# ETHERNET_W5500.net
KiCad netlist of a schematic drawn in Altium Designer
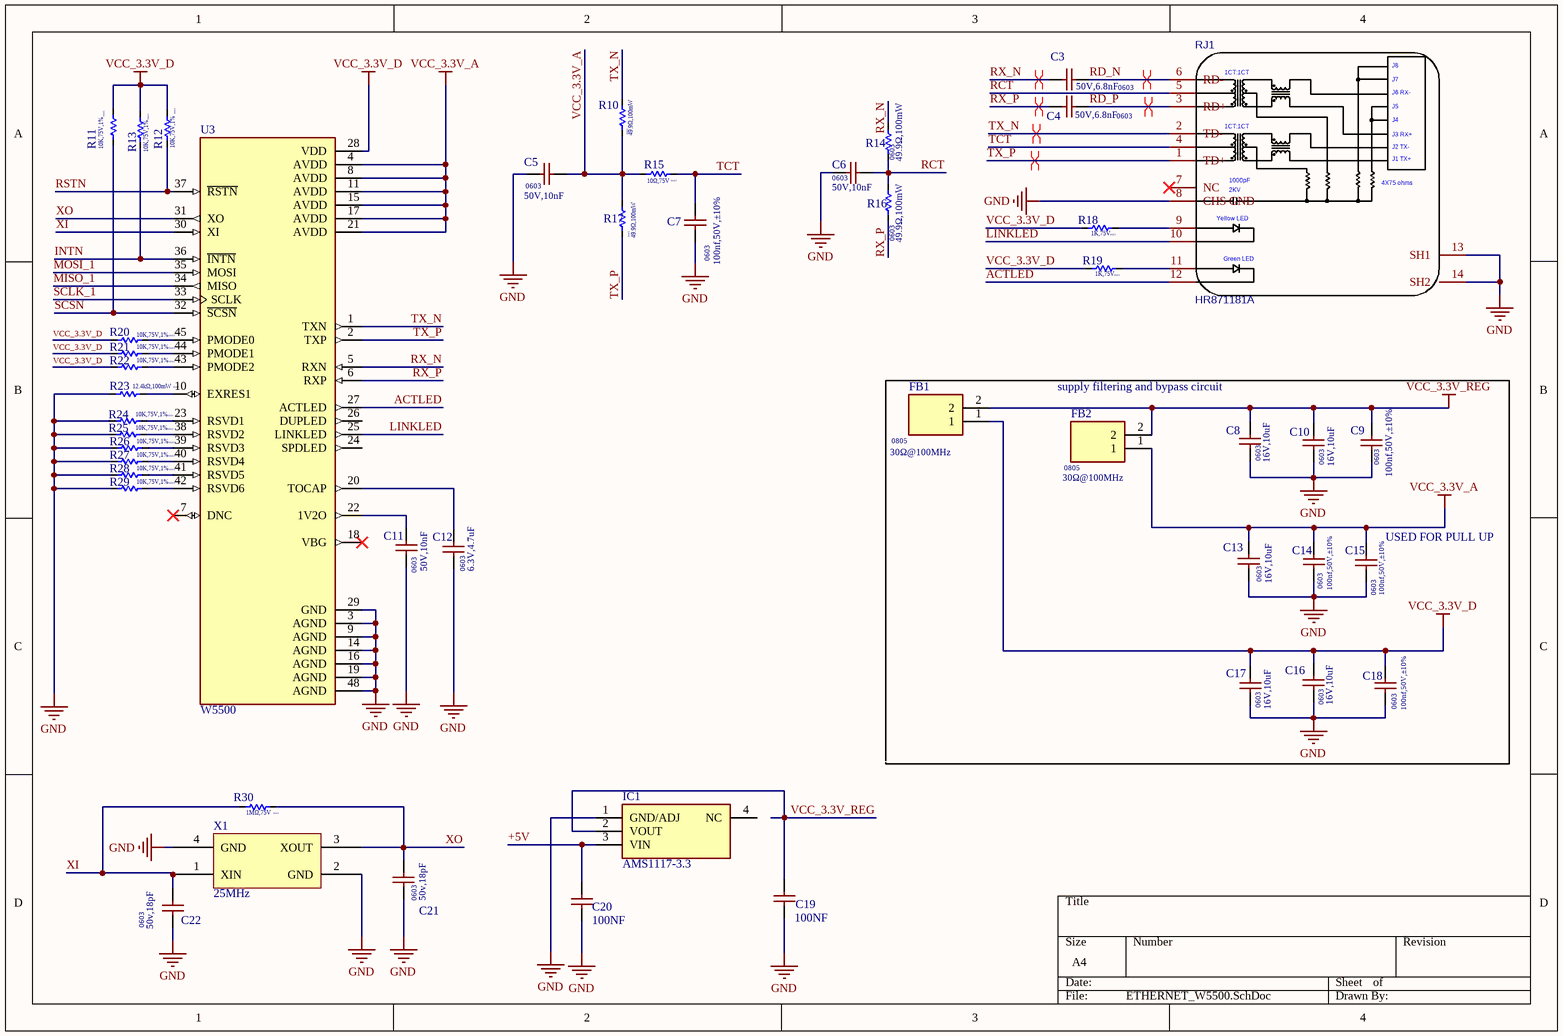
[diagram p0: ETHERNET_W5500.SchDoc]

(export (version "E")
  (design (tool "Eeschema 10.0.6"))
  (components
    (comp (ref "C3")
      (value "50V,6.8nF")
      (footprint "CAPC1608X90N")
      (description "50V 6.8nF X7R ±10% 0603 Multilayer Ceramic Capacitors MLCC - SMD/SMT ROHS")
      (fields
        (field (name "MANUFACTURER") "Walsin Tech Corp")
        (field (name "MPN") "0603B682K500CT")
        (field (name "PACKAGE") "0603")
      )
      (libsource (lib "RCL") (part "0603B682K500CT"))
    )
    (comp (ref "C4")
      (value "50V,6.8nF")
      (footprint "CAPC1608X90N")
      (description "50V 6.8nF X7R ±10% 0603 Multilayer Ceramic Capacitors MLCC - SMD/SMT ROHS")
      (fields
        (field (name "MANUFACTURER") "Walsin Tech Corp")
        (field (name "MPN") "0603B682K500CT")
        (field (name "PACKAGE") "0603")
      )
      (libsource (lib "RCL") (part "0603B682K500CT"))
    )
    (comp (ref "C5")
      (value "50V,10nF")
      (footprint "CAPC1608X90N")
      (description "50V 10nF X7R ±20% 0603 Multilayer Ceramic Capacitors MLCC - SMD/SMT ROHS")
      (fields
        (field (name "MANUFACTURER") "CCTC")
        (field (name "MPN") "TCC0603X7R103M500CT")
        (field (name "PACKAGE") "0603")
      )
      (libsource (lib "RCL") (part "TCC0603X7R103M500CT"))
    )
    (comp (ref "C6")
      (value "50V,10nF")
      (footprint "CAPC1608X90N")
      (description "50V 10nF X7R ±20% 0603 Multilayer Ceramic Capacitors MLCC - SMD/SMT ROHS")
      (fields
        (field (name "MANUFACTURER") "CCTC")
        (field (name "MPN") "TCC0603X7R103M500CT")
        (field (name "PACKAGE") "0603")
      )
      (libsource (lib "RCL") (part "TCC0603X7R103M500CT"))
    )
    (comp (ref "C7")
      (value "100nf,50V,±10%")
      (footprint "C0603")
      (description "50V 100nF X7R ±10% 0603 Multilayer Ceramic Capacitors MLCC - SMD/SMT ROHS")
      (fields
        (field (name "MPN") "603-CC603KRX7R9BB104")
        (field (name "MANUFACTURER") "KEMET")
        (field (name "PACKAGE") "0603")
      )
      (libsource (lib "RCL") (part "CC0603KRX7R9BB104"))
    )
    (comp (ref "C8")
      (value "16V,10uF")
      (footprint "CAPC1608X90N")
      (description "16V 10uF Y5V ±20% 0603 Multilayer Ceramic Capacitors MLCC - SMD/SMT ROHS")
      (fields
        (field (name "MANUFACTURER") "KEMET")
        (field (name "MPN") "CC0603KRX7R9BB104")
        (field (name "PACKAGE") "0603")
      )
      (libsource (lib "RCL") (part "0603F106M160NT"))
    )
    (comp (ref "C9")
      (value "100nf,50V,±10%")
      (footprint "C0603")
      (description "50V 100nF X7R ±10% 0603 Multilayer Ceramic Capacitors MLCC - SMD/SMT ROHS")
      (fields
        (field (name "MPN") "603-CC603KRX7R9BB104")
        (field (name "MANUFACTURER") "KEMET")
        (field (name "PACKAGE") "0603")
      )
      (libsource (lib "RCL") (part "CC0603KRX7R9BB104"))
    )
    (comp (ref "C10")
      (value "16V,10uF")
      (footprint "CAPC1608X90N")
      (description "16V 10uF Y5V ±20% 0603 Multilayer Ceramic Capacitors MLCC - SMD/SMT ROHS")
      (fields
        (field (name "MANUFACTURER") "KEMET")
        (field (name "MPN") "CC0603KRX7R9BB104")
        (field (name "PACKAGE") "0603")
      )
      (libsource (lib "RCL") (part "0603F106M160NT"))
    )
    (comp (ref "C11")
      (value "50V,10nF")
      (footprint "CAPC1608X90N")
      (description "50V 10nF X7R ±20% 0603 Multilayer Ceramic Capacitors MLCC - SMD/SMT ROHS")
      (fields
        (field (name "MANUFACTURER") "CCTC")
        (field (name "MPN") "TCC0603X7R103M500CT")
        (field (name "PACKAGE") "0603")
      )
      (libsource (lib "RCL") (part "TCC0603X7R103M500CT"))
    )
    (comp (ref "C12")
      (value "6.3V,4.7uF")
      (footprint "CAPC1608X90N")
      (description "Capacitor")
      (fields
        (field (name "MANUFACTURER") "Samsung Electro-Mechanics")
        (field (name "MPN") "CL10A475KQ8NNNC")
        (field (name "PACKAGE") "0603")
      )
      (libsource (lib "RCL") (part "CL10A475KQ8NNNC"))
    )
    (comp (ref "C13")
      (value "16V,10uF")
      (footprint "CAPC1608X90N")
      (description "16V 10uF Y5V ±20% 0603 Multilayer Ceramic Capacitors MLCC - SMD/SMT ROHS")
      (fields
        (field (name "MANUFACTURER") "KEMET")
        (field (name "MPN") "CC0603KRX7R9BB104")
        (field (name "PACKAGE") "0603")
      )
      (libsource (lib "RCL") (part "0603F106M160NT"))
    )
    (comp (ref "C14")
      (value "100nf,50V,±10%")
      (footprint "C0603")
      (description "50V 100nF X7R ±10% 0603 Multilayer Ceramic Capacitors MLCC - SMD/SMT ROHS")
      (fields
        (field (name "MPN") "603-CC603KRX7R9BB104")
        (field (name "MANUFACTURER") "KEMET")
        (field (name "PACKAGE") "0603")
      )
      (libsource (lib "RCL") (part "CC0603KRX7R9BB104"))
    )
    (comp (ref "C15")
      (value "100nf,50V,±10%")
      (footprint "C0603")
      (description "50V 100nF X7R ±10% 0603 Multilayer Ceramic Capacitors MLCC - SMD/SMT ROHS")
      (fields
        (field (name "MPN") "603-CC603KRX7R9BB104")
        (field (name "MANUFACTURER") "KEMET")
        (field (name "PACKAGE") "0603")
      )
      (libsource (lib "RCL") (part "CC0603KRX7R9BB104"))
    )
    (comp (ref "C16")
      (value "16V,10uF")
      (footprint "CAPC1608X90N")
      (description "16V 10uF Y5V ±20% 0603 Multilayer Ceramic Capacitors MLCC - SMD/SMT ROHS")
      (fields
        (field (name "MANUFACTURER") "KEMET")
        (field (name "MPN") "CC0603KRX7R9BB104")
        (field (name "PACKAGE") "0603")
      )
      (libsource (lib "RCL") (part "0603F106M160NT"))
    )
    (comp (ref "C17")
      (value "16V,10uF")
      (footprint "CAPC1608X90N")
      (description "16V 10uF Y5V ±20% 0603 Multilayer Ceramic Capacitors MLCC - SMD/SMT ROHS")
      (fields
        (field (name "MANUFACTURER") "KEMET")
        (field (name "MPN") "CC0603KRX7R9BB104")
        (field (name "PACKAGE") "0603")
      )
      (libsource (lib "RCL") (part "0603F106M160NT"))
    )
    (comp (ref "C18")
      (value "100nf,50V,±10%")
      (footprint "C0603")
      (description "50V 100nF X7R ±10% 0603 Multilayer Ceramic Capacitors MLCC - SMD/SMT ROHS")
      (fields
        (field (name "MPN") "603-CC603KRX7R9BB104")
        (field (name "MANUFACTURER") "KEMET")
        (field (name "PACKAGE") "0603")
      )
      (libsource (lib "RCL") (part "CC0603KRX7R9BB104"))
    )
    (comp (ref "C19")
      (value "100NF")
      (footprint "C0603")
      (description "50V 100nF X7R ±10% 0603 Multilayer Ceramic Capacitors MLCC - SMD/SMT ROHS")
      (fields (field (name "MPN") "603-CC603KRX7R9BB104") (field (name "MANUFACTURER") "KEMET"))
      (libsource (lib "RCL") (part "CC0603KRX7R9BB104"))
    )
    (comp (ref "C20")
      (value "100NF")
      (footprint "C0603")
      (description "50V 100nF X7R ±10% 0603 Multilayer Ceramic Capacitors MLCC - SMD/SMT ROHS")
      (fields (field (name "MPN") "603-CC603KRX7R9BB104") (field (name "MANUFACTURER") "KEMET"))
      (libsource (lib "RCL") (part "CC0603KRX7R9BB104"))
    )
    (comp (ref "C21")
      (value "50v,18pF")
      (footprint "CAPC1608X90N")
      (description "50V 18pF NP0 ±5% 0603 Multilayer Ceramic Capacitors MLCC - SMD/SMT ROHS")
      (fields
        (field (name "MANUFACTURER") "YAGEO")
        (field (name "MPN") "CC0603JRNPO9BN180")
        (field (name "PACKAGE") "0603")
      )
      (libsource (lib "RCL") (part "CC0603JRNPO9BN180"))
    )
    (comp (ref "C22")
      (value "50v,18pF")
      (footprint "CAPC1608X90N")
      (description "50V 18pF NP0 ±5% 0603 Multilayer Ceramic Capacitors MLCC - SMD/SMT ROHS")
      (fields
        (field (name "MANUFACTURER") "YAGEO")
        (field (name "MPN") "CC0603JRNPO9BN180")
        (field (name "PACKAGE") "0603")
      )
      (libsource (lib "RCL") (part "CC0603JRNPO9BN180"))
    )
    (comp (ref "FB1")
      (value "30Ω@100MHz")
      (footprint "BEADC2012X105N")
      (description "Ferrite Bead")
      (fields
        (field (name "MANUFACTURER") "Murata Electronics")
        (field (name "MPN") "BLM21PG300SN1D")
        (field (name "PACKAGE") "0805")
      )
      (libsource (lib "RCL") (part "BLM21PG300SN1D"))
    )
    (comp (ref "FB2")
      (value "30Ω@100MHz")
      (footprint "BEADC2012X105N")
      (description "Ferrite Bead")
      (fields
        (field (name "MANUFACTURER") "Murata Electronics")
        (field (name "MPN") "BLM21PG300SN1D")
        (field (name "PACKAGE") "0805")
      )
      (libsource (lib "RCL") (part "BLM21PG300SN1D"))
    )
    (comp (ref "IC1")
      (value "AMS1117-3.3")
      (footprint "IC:SOT229P700X180-4N")
      (description "Integrated Circuit")
      (fields (field (name "MANUFACTURER") "Advanced"))
      (libsource (lib "IC") (part "AMS1117-3.3"))
    )
    (comp (ref "R10")
      (value "49.9Ω,100mW")
      (footprint "R0603")
      (description "100mW Thick Film Resistors ±100ppm/℃ ±1% 49.9Ω 0603 Chip Resistor - Surface Mount ROHS")
      (fields
        (field (name "MANUFACTURER") "Panasonic")
        (field (name "MPN") "ERJ-3EKF49R9V")
        (field (name "PACKAGE") "0603")
      )
      (libsource (lib "RCL") (part "ERJ-3EKF49R9V"))
    )
    (comp (ref "R11")
      (value "10K,75V,1%")
      (footprint "R0603")
      (description "100mW Thick Film Resistors ±100ppm/℃ ±1% 10kΩ 0603 Chip Resistor - Surface Mount ROHS")
      (fields
        (field (name "MPN") "0603WAF1002T5E")
        (field (name "MANUFACTURER") "UNI-ROYAL(Uniroyal Elec)")
        (field (name "PACKAGE") "0603")
      )
      (libsource (lib "RCL") (part "0603WAF1002T5E"))
    )
    (comp (ref "R12")
      (value "10K,75V,1%")
      (footprint "R0603")
      (description "100mW Thick Film Resistors ±100ppm/℃ ±1% 10kΩ 0603 Chip Resistor - Surface Mount ROHS")
      (fields
        (field (name "MPN") "0603WAF1002T5E")
        (field (name "MANUFACTURER") "UNI-ROYAL(Uniroyal Elec)")
        (field (name "PACKAGE") "0603")
      )
      (libsource (lib "RCL") (part "0603WAF1002T5E"))
    )
    (comp (ref "R13")
      (value "10K,75V,1%")
      (footprint "R0603")
      (description "100mW Thick Film Resistors ±100ppm/℃ ±1% 10kΩ 0603 Chip Resistor - Surface Mount ROHS")
      (fields
        (field (name "MPN") "0603WAF1002T5E")
        (field (name "MANUFACTURER") "UNI-ROYAL(Uniroyal Elec)")
        (field (name "PACKAGE") "0603")
      )
      (libsource (lib "RCL") (part "0603WAF1002T5E"))
    )
    (comp (ref "R14")
      (value "49.9Ω,100mW")
      (footprint "R0603")
      (description "100mW Thick Film Resistors ±100ppm/℃ ±1% 49.9Ω 0603 Chip Resistor - Surface Mount ROHS")
      (fields
        (field (name "MANUFACTURER") "Panasonic")
        (field (name "MPN") "ERJ-3EKF49R9V")
        (field (name "PACKAGE") "0603")
      )
      (libsource (lib "RCL") (part "ERJ-3EKF49R9V"))
    )
    (comp (ref "R15")
      (value "10Ω,75V")
      (footprint "R0603")
      (fields
        (field (name "MANUFACTURER") "Ever Ohms Tech")
        (field (name "MPN") "QR0603J10R0P05Z")
        (field (name "PACKAGE") "0603")
        (field (name "Comment") "10R")
      )
      (libsource (lib "RCL") (part "QR0603J10R0P05Z"))
    )
    (comp (ref "R16")
      (value "49.9Ω,100mW")
      (footprint "R0603")
      (description "100mW Thick Film Resistors ±100ppm/℃ ±1% 49.9Ω 0603 Chip Resistor - Surface Mount ROHS")
      (fields
        (field (name "MANUFACTURER") "Panasonic")
        (field (name "MPN") "ERJ-3EKF49R9V")
        (field (name "PACKAGE") "0603")
      )
      (libsource (lib "RCL") (part "ERJ-3EKF49R9V"))
    )
    (comp (ref "R17")
      (value "49.9Ω,100mW")
      (footprint "R0603")
      (description "100mW Thick Film Resistors ±100ppm/℃ ±1% 49.9Ω 0603 Chip Resistor - Surface Mount ROHS")
      (fields
        (field (name "MANUFACTURER") "Panasonic")
        (field (name "MPN") "ERJ-3EKF49R9V")
        (field (name "PACKAGE") "0603")
      )
      (libsource (lib "RCL") (part "ERJ-3EKF49R9V"))
    )
    (comp (ref "R18")
      (value "1K,75V")
      (footprint "R0603")
      (description "100mW Thick Film Resistors 75V ±100ppm/℃ ±1% 1kΩ 0603 Chip Resistor - Surface Mount ROHS")
      (fields
        (field (name "MANUFACTURER") "UNI-ROYAL(Uniroyal Elec)")
        (field (name "MPN") "0603WAF1001T5E")
        (field (name "PACKAGE") "0603")
      )
      (libsource (lib "RCL") (part "0603WAF1001T5E"))
    )
    (comp (ref "R19")
      (value "1K,75V")
      (footprint "R0603")
      (description "100mW Thick Film Resistors 75V ±100ppm/℃ ±1% 1kΩ 0603 Chip Resistor - Surface Mount ROHS")
      (fields
        (field (name "MANUFACTURER") "UNI-ROYAL(Uniroyal Elec)")
        (field (name "MPN") "0603WAF1001T5E")
        (field (name "PACKAGE") "0603")
      )
      (libsource (lib "RCL") (part "0603WAF1001T5E"))
    )
    (comp (ref "R20")
      (value "10K,75V,1%")
      (footprint "R0603")
      (description "100mW Thick Film Resistors ±100ppm/℃ ±1% 10kΩ 0603 Chip Resistor - Surface Mount ROHS")
      (fields
        (field (name "MPN") "0603WAF1002T5E")
        (field (name "MANUFACTURER") "UNI-ROYAL(Uniroyal Elec)")
        (field (name "PACKAGE") "0603")
      )
      (libsource (lib "RCL") (part "0603WAF1002T5E"))
    )
    (comp (ref "R21")
      (value "10K,75V,1%")
      (footprint "R0603")
      (description "100mW Thick Film Resistors ±100ppm/℃ ±1% 10kΩ 0603 Chip Resistor - Surface Mount ROHS")
      (fields
        (field (name "MPN") "0603WAF1002T5E")
        (field (name "MANUFACTURER") "UNI-ROYAL(Uniroyal Elec)")
        (field (name "PACKAGE") "0603")
      )
      (libsource (lib "RCL") (part "0603WAF1002T5E"))
    )
    (comp (ref "R22")
      (value "10K,75V,1%")
      (footprint "R0603")
      (description "100mW Thick Film Resistors ±100ppm/℃ ±1% 10kΩ 0603 Chip Resistor - Surface Mount ROHS")
      (fields
        (field (name "MPN") "0603WAF1002T5E")
        (field (name "MANUFACTURER") "UNI-ROYAL(Uniroyal Elec)")
        (field (name "PACKAGE") "0603")
      )
      (libsource (lib "RCL") (part "0603WAF1002T5E"))
    )
    (comp (ref "R23")
      (value "12.4kΩ,100mW")
      (footprint "R0603")
      (description "Resistor")
      (fields
        (field (name "MANUFACTURER") "Panasonic")
        (field (name "MPN") "ERJ-3EKF1242V")
        (field (name "PACKAGE") "0603")
      )
      (libsource (lib "RCL") (part "ERJ-3EKF1242V"))
    )
    (comp (ref "R24")
      (value "10K,75V,1%")
      (footprint "R0603")
      (description "100mW Thick Film Resistors ±100ppm/℃ ±1% 10kΩ 0603 Chip Resistor - Surface Mount ROHS")
      (fields
        (field (name "MPN") "0603WAF1002T5E")
        (field (name "MANUFACTURER") "UNI-ROYAL(Uniroyal Elec)")
        (field (name "PACKAGE") "0603")
      )
      (libsource (lib "RCL") (part "0603WAF1002T5E"))
    )
    (comp (ref "R25")
      (value "10K,75V,1%")
      (footprint "R0603")
      (description "100mW Thick Film Resistors ±100ppm/℃ ±1% 10kΩ 0603 Chip Resistor - Surface Mount ROHS")
      (fields
        (field (name "MPN") "0603WAF1002T5E")
        (field (name "MANUFACTURER") "UNI-ROYAL(Uniroyal Elec)")
        (field (name "PACKAGE") "0603")
      )
      (libsource (lib "RCL") (part "0603WAF1002T5E"))
    )
    (comp (ref "R26")
      (value "10K,75V,1%")
      (footprint "R0603")
      (description "100mW Thick Film Resistors ±100ppm/℃ ±1% 10kΩ 0603 Chip Resistor - Surface Mount ROHS")
      (fields
        (field (name "MPN") "0603WAF1002T5E")
        (field (name "MANUFACTURER") "UNI-ROYAL(Uniroyal Elec)")
        (field (name "PACKAGE") "0603")
      )
      (libsource (lib "RCL") (part "0603WAF1002T5E"))
    )
    (comp (ref "R27")
      (value "10K,75V,1%")
      (footprint "R0603")
      (description "100mW Thick Film Resistors ±100ppm/℃ ±1% 10kΩ 0603 Chip Resistor - Surface Mount ROHS")
      (fields
        (field (name "MPN") "0603WAF1002T5E")
        (field (name "MANUFACTURER") "UNI-ROYAL(Uniroyal Elec)")
        (field (name "PACKAGE") "0603")
      )
      (libsource (lib "RCL") (part "0603WAF1002T5E"))
    )
    (comp (ref "R28")
      (value "10K,75V,1%")
      (footprint "R0603")
      (description "100mW Thick Film Resistors ±100ppm/℃ ±1% 10kΩ 0603 Chip Resistor - Surface Mount ROHS")
      (fields
        (field (name "MPN") "0603WAF1002T5E")
        (field (name "MANUFACTURER") "UNI-ROYAL(Uniroyal Elec)")
        (field (name "PACKAGE") "0603")
      )
      (libsource (lib "RCL") (part "0603WAF1002T5E"))
    )
    (comp (ref "R29")
      (value "10K,75V,1%")
      (footprint "R0603")
      (description "100mW Thick Film Resistors ±100ppm/℃ ±1% 10kΩ 0603 Chip Resistor - Surface Mount ROHS")
      (fields
        (field (name "MPN") "0603WAF1002T5E")
        (field (name "MANUFACTURER") "UNI-ROYAL(Uniroyal Elec)")
        (field (name "PACKAGE") "0603")
      )
      (libsource (lib "RCL") (part "0603WAF1002T5E"))
    )
    (comp (ref "R30")
      (value "1MΩ,75V")
      (footprint "R0603")
      (description "100mW Thick Film Resistors ±100ppm/℃ ±1% 1MΩ 0603 Chip Resistor - Surface Mount ROHS")
      (fields
        (field (name "MANUFACTURER") "UNI-ROYAL(Uniroyal Elec)")
        (field (name "MPN") "0603WAF1002T5E")
        (field (name "PACKAGE") "0603")
      )
      (libsource (lib "RCL") (part "0603WAF1004T5E"))
    )
    (comp (ref "RJ1")
      (value "HR871181A")
      (footprint "HR871181A_mirror")
      (fields (field (name "BOM_SUPPLIER PART") "C49312"))
      (libsource (lib "connector_button") (part "HR871181A_mirror"))
    )
    (comp (ref "U3")
      (value "W5500")
      (footprint "W5500 Ethernet")
      (description "Ethernet Controller 10/100 Base-T/TX PHY SPI Interface 48-LQFP (7x7)")
      (fields (field (name "MF") "WIZnet"))
      (libsource (lib "IC_MODULE") (part "W5500"))
    )
    (comp (ref "X1")
      (value "25MHz")
      (footprint "SMD Crystal")
      (description "25MHz SMD Crystal Resonator 18pF 60Ω ±10ppm ±30ppm -40℃~+85℃ SMD3225-4P Crystals ROHS")
      (libsource (lib "RCL") (part "3TJ425000XYFBC"))
    )
  )
  (nets
    (net (code "1") (name "/+5V") (class "Default")
      (node (ref "C20") (pin "1") (pinfunction "1_1") (pintype "passive"))
      (node (ref "IC1") (pin "3") (pinfunction "VIN_3") (pintype "passive"))
    )
    (net (code "2") (name "/ACTLED") (class "Default")
      (node (ref "RJ1") (pin "12") (pinfunction "12_12") (pintype "passive"))
      (node (ref "U3") (pin "27") (pinfunction "ACTLED_27") (pintype "output"))
    )
    (net (code "3") (name "/INTN") (class "Default")
      (node (ref "R13") (pin "1") (pinfunction "1_1") (pintype "passive"))
      (node (ref "U3") (pin "36") (pinfunction "~{INTN}_36") (pintype "input"))
    )
    (net (code "4") (name "/LINKLED") (class "Default")
      (node (ref "RJ1") (pin "10") (pinfunction "10_10") (pintype "passive"))
      (node (ref "U3") (pin "25") (pinfunction "LINKLED_25") (pintype "output"))
    )
    (net (code "5") (name "/MISO_1") (class "Default")
      (node (ref "U3") (pin "34") (pinfunction "MISO_34") (pintype "output"))
    )
    (net (code "6") (name "/MOSI_1") (class "Default")
      (node (ref "U3") (pin "35") (pinfunction "MOSI_35") (pintype "input"))
    )
    (net (code "7") (name "/RCT") (class "Default")
      (node (ref "C6") (pin "2") (pinfunction "2_2") (pintype "passive"))
      (node (ref "R14") (pin "1") (pinfunction "1_1") (pintype "passive"))
      (node (ref "R16") (pin "2") (pinfunction "2_2") (pintype "passive"))
      (node (ref "RJ1") (pin "5") (pinfunction "5_5") (pintype "passive"))
    )
    (net (code "8") (name "/RD_N") (class "Default")
      (node (ref "C3") (pin "2") (pinfunction "2_2") (pintype "passive"))
      (node (ref "RJ1") (pin "6") (pinfunction "RD-_6") (pintype "passive"))
    )
    (net (code "9") (name "/RD_P") (class "Default")
      (node (ref "C4") (pin "2") (pinfunction "2_2") (pintype "passive"))
      (node (ref "RJ1") (pin "3") (pinfunction "RD+_3") (pintype "passive"))
    )
    (net (code "10") (name "/RSTN") (class "Default")
      (node (ref "R12") (pin "1") (pinfunction "1_1") (pintype "passive"))
      (node (ref "U3") (pin "37") (pinfunction "~{RSTN}_37") (pintype "input"))
    )
    (net (code "11") (name "/RX_N") (class "Default")
      (node (ref "C3") (pin "1") (pinfunction "1_1") (pintype "passive"))
      (node (ref "R14") (pin "2") (pinfunction "2_2") (pintype "passive"))
      (node (ref "U3") (pin "5") (pinfunction "RXN_5") (pintype "input"))
    )
    (net (code "12") (name "/RX_P") (class "Default")
      (node (ref "C4") (pin "1") (pinfunction "1_1") (pintype "passive"))
      (node (ref "R16") (pin "1") (pinfunction "1_1") (pintype "passive"))
      (node (ref "U3") (pin "6") (pinfunction "RXP_6") (pintype "input"))
    )
    (net (code "13") (name "/SCLK_1") (class "Default")
      (node (ref "U3") (pin "33") (pinfunction "SCLK_33") (pintype "input"))
    )
    (net (code "14") (name "/SCSN") (class "Default")
      (node (ref "R11") (pin "1") (pinfunction "1_1") (pintype "passive"))
      (node (ref "U3") (pin "32") (pinfunction "~{SCSN}_32") (pintype "input"))
    )
    (net (code "15") (name "/TCT") (class "Default")
      (node (ref "C7") (pin "2") (pinfunction "2_2") (pintype "passive"))
      (node (ref "R15") (pin "2") (pinfunction "2_2") (pintype "passive"))
      (node (ref "RJ1") (pin "4") (pinfunction "4_4") (pintype "passive"))
    )
    (net (code "16") (name "/TX_N") (class "Default")
      (node (ref "R10") (pin "2") (pinfunction "2_2") (pintype "passive"))
      (node (ref "RJ1") (pin "2") (pinfunction "TD-_2") (pintype "passive"))
      (node (ref "U3") (pin "1") (pinfunction "TXN_1") (pintype "output"))
    )
    (net (code "17") (name "/TX_P") (class "Default")
      (node (ref "R17") (pin "1") (pinfunction "1_1") (pintype "passive"))
      (node (ref "RJ1") (pin "1") (pinfunction "TD+_1") (pintype "passive"))
      (node (ref "U3") (pin "2") (pinfunction "TXP_2") (pintype "output"))
    )
    (net (code "18") (name "/XI") (class "Default")
      (node (ref "C22") (pin "1") (pinfunction "1_1") (pintype "passive"))
      (node (ref "R30") (pin "1") (pinfunction "1_1") (pintype "passive"))
      (node (ref "U3") (pin "30") (pinfunction "XI_30") (pintype "input"))
      (node (ref "X1") (pin "1") (pinfunction "XIN_1") (pintype "passive"))
    )
    (net (code "19") (name "/XO") (class "Default")
      (node (ref "C21") (pin "1") (pinfunction "1_1") (pintype "passive"))
      (node (ref "R30") (pin "2") (pinfunction "2_2") (pintype "passive"))
      (node (ref "U3") (pin "31") (pinfunction "XO_31") (pintype "output"))
      (node (ref "X1") (pin "3") (pinfunction "XOUT_3") (pintype "passive"))
    )
    (net (code "20") (name "GND") (class "Default")
      (node (ref "C10") (pin "1") (pinfunction "1_1") (pintype "passive"))
      (node (ref "C11") (pin "2") (pinfunction "2_2") (pintype "passive"))
      (node (ref "C12") (pin "2") (pinfunction "2_2") (pintype "passive"))
      (node (ref "C13") (pin "1") (pinfunction "1_1") (pintype "passive"))
      (node (ref "C14") (pin "1") (pinfunction "1_1") (pintype "passive"))
      (node (ref "C15") (pin "1") (pinfunction "1_1") (pintype "passive"))
      (node (ref "C16") (pin "1") (pinfunction "1_1") (pintype "passive"))
      (node (ref "C17") (pin "1") (pinfunction "1_1") (pintype "passive"))
      (node (ref "C18") (pin "1") (pinfunction "1_1") (pintype "passive"))
      (node (ref "C19") (pin "2") (pinfunction "2_2") (pintype "passive"))
      (node (ref "C20") (pin "2") (pinfunction "2_2") (pintype "passive"))
      (node (ref "C21") (pin "2") (pinfunction "2_2") (pintype "passive"))
      (node (ref "C22") (pin "2") (pinfunction "2_2") (pintype "passive"))
      (node (ref "C5") (pin "1") (pinfunction "1_1") (pintype "passive"))
      (node (ref "C6") (pin "1") (pinfunction "1_1") (pintype "passive"))
      (node (ref "C7") (pin "1") (pinfunction "1_1") (pintype "passive"))
      (node (ref "C8") (pin "1") (pinfunction "1_1") (pintype "passive"))
      (node (ref "C9") (pin "1") (pinfunction "1_1") (pintype "passive"))
      (node (ref "IC1") (pin "1") (pinfunction "GND/ADJ_1") (pintype "passive"))
      (node (ref "R23") (pin "1") (pinfunction "1_1") (pintype "passive"))
      (node (ref "R24") (pin "2") (pinfunction "2_2") (pintype "passive"))
      (node (ref "R25") (pin "2") (pinfunction "2_2") (pintype "passive"))
      (node (ref "R26") (pin "2") (pinfunction "2_2") (pintype "passive"))
      (node (ref "R27") (pin "2") (pinfunction "2_2") (pintype "passive"))
      (node (ref "R28") (pin "2") (pinfunction "2_2") (pintype "passive"))
      (node (ref "R29") (pin "2") (pinfunction "2_2") (pintype "passive"))
      (node (ref "RJ1") (pin "13") (pinfunction "SH1_13") (pintype "passive"))
      (node (ref "RJ1") (pin "14") (pinfunction "SH2_14") (pintype "passive"))
      (node (ref "RJ1") (pin "8") (pinfunction "CHS_GND_8") (pintype "passive"))
      (node (ref "U3") (pin "14") (pinfunction "AGND_14") (pintype "power_in"))
      (node (ref "U3") (pin "16") (pinfunction "AGND_16") (pintype "power_in"))
      (node (ref "U3") (pin "19") (pinfunction "AGND_19") (pintype "power_in"))
      (node (ref "U3") (pin "29") (pinfunction "GND_29") (pintype "passive"))
      (node (ref "U3") (pin "3") (pinfunction "AGND_3") (pintype "power_in"))
      (node (ref "U3") (pin "48") (pinfunction "AGND_48") (pintype "power_in"))
      (node (ref "U3") (pin "9") (pinfunction "AGND_9") (pintype "power_in"))
      (node (ref "X1") (pin "2") (pinfunction "GND_2") (pintype "passive"))
      (node (ref "X1") (pin "4") (pinfunction "GND_4") (pintype "passive"))
    )
    (net (code "21") (name "Net-(R18-Pad2)") (class "Default")
      (node (ref "R18") (pin "2") (pinfunction "2_2") (pintype "passive"))
      (node (ref "RJ1") (pin "9") (pinfunction "9_9") (pintype "passive"))
    )
    (net (code "22") (name "Net-(R19-Pad2)") (class "Default")
      (node (ref "R19") (pin "2") (pinfunction "2_2") (pintype "passive"))
      (node (ref "RJ1") (pin "11") (pinfunction "11_11") (pintype "passive"))
    )
    (net (code "23") (name "Net-(U3-1V2O)") (class "Default")
      (node (ref "C11") (pin "1") (pinfunction "1_1") (pintype "passive"))
      (node (ref "U3") (pin "22") (pinfunction "1V2O_22") (pintype "output"))
    )
    (net (code "24") (name "Net-(U3-EXRES1)") (class "Default")
      (node (ref "R23") (pin "2") (pinfunction "2_2") (pintype "passive"))
      (node (ref "U3") (pin "10") (pinfunction "EXRES1_10") (pintype "bidirectional"))
    )
    (net (code "25") (name "Net-(U3-PMODE0)") (class "Default")
      (node (ref "R20") (pin "1") (pinfunction "1_1") (pintype "passive"))
      (node (ref "U3") (pin "45") (pinfunction "PMODE0_45") (pintype "input"))
    )
    (net (code "26") (name "Net-(U3-PMODE1)") (class "Default")
      (node (ref "R21") (pin "1") (pinfunction "1_1") (pintype "passive"))
      (node (ref "U3") (pin "44") (pinfunction "PMODE1_44") (pintype "input"))
    )
    (net (code "27") (name "Net-(U3-PMODE2)") (class "Default")
      (node (ref "R22") (pin "1") (pinfunction "1_1") (pintype "passive"))
      (node (ref "U3") (pin "43") (pinfunction "PMODE2_43") (pintype "input"))
    )
    (net (code "28") (name "Net-(U3-RSVD1)") (class "Default")
      (node (ref "R24") (pin "1") (pinfunction "1_1") (pintype "passive"))
      (node (ref "U3") (pin "23") (pinfunction "RSVD1_23") (pintype "input"))
    )
    (net (code "29") (name "Net-(U3-RSVD2)") (class "Default")
      (node (ref "R25") (pin "1") (pinfunction "1_1") (pintype "passive"))
      (node (ref "U3") (pin "38") (pinfunction "RSVD2_38") (pintype "input"))
    )
    (net (code "30") (name "Net-(U3-RSVD3)") (class "Default")
      (node (ref "R26") (pin "1") (pinfunction "1_1") (pintype "passive"))
      (node (ref "U3") (pin "39") (pinfunction "RSVD3_39") (pintype "input"))
    )
    (net (code "31") (name "Net-(U3-RSVD4)") (class "Default")
      (node (ref "R27") (pin "1") (pinfunction "1_1") (pintype "passive"))
      (node (ref "U3") (pin "40") (pinfunction "RSVD4_40") (pintype "input"))
    )
    (net (code "32") (name "Net-(U3-RSVD5)") (class "Default")
      (node (ref "R28") (pin "1") (pinfunction "1_1") (pintype "passive"))
      (node (ref "U3") (pin "41") (pinfunction "RSVD5_41") (pintype "input"))
    )
    (net (code "33") (name "Net-(U3-RSVD6)") (class "Default")
      (node (ref "R29") (pin "1") (pinfunction "1_1") (pintype "passive"))
      (node (ref "U3") (pin "42") (pinfunction "RSVD6_42") (pintype "input"))
    )
    (net (code "34") (name "Net-(U3-TOCAP)") (class "Default")
      (node (ref "C12") (pin "1") (pinfunction "1_1") (pintype "passive"))
      (node (ref "U3") (pin "20") (pinfunction "TOCAP_20") (pintype "output"))
    )
    (net (code "35") (name "VCC_3.3V_A") (class "Default")
      (node (ref "C13") (pin "2") (pinfunction "2_2") (pintype "passive"))
      (node (ref "C14") (pin "2") (pinfunction "2_2") (pintype "passive"))
      (node (ref "C15") (pin "2") (pinfunction "2_2") (pintype "passive"))
      (node (ref "C5") (pin "2") (pinfunction "2_2") (pintype "passive"))
      (node (ref "FB2") (pin "1") (pinfunction "1_1") (pintype "passive"))
      (node (ref "R10") (pin "1") (pinfunction "1_1") (pintype "passive"))
      (node (ref "R15") (pin "1") (pinfunction "1_1") (pintype "passive"))
      (node (ref "R17") (pin "2") (pinfunction "2_2") (pintype "passive"))
      (node (ref "U3") (pin "11") (pinfunction "AVDD_11") (pintype "power_in"))
      (node (ref "U3") (pin "15") (pinfunction "AVDD_15") (pintype "power_in"))
      (node (ref "U3") (pin "17") (pinfunction "AVDD_17") (pintype "power_in"))
      (node (ref "U3") (pin "21") (pinfunction "AVDD_21") (pintype "power_in"))
      (node (ref "U3") (pin "4") (pinfunction "AVDD_4") (pintype "power_in"))
      (node (ref "U3") (pin "8") (pinfunction "AVDD_8") (pintype "power_in"))
    )
    (net (code "36") (name "VCC_3.3V_D") (class "Default")
      (node (ref "C16") (pin "2") (pinfunction "2_2") (pintype "passive"))
      (node (ref "C17") (pin "2") (pinfunction "2_2") (pintype "passive"))
      (node (ref "C18") (pin "2") (pinfunction "2_2") (pintype "passive"))
      (node (ref "FB1") (pin "1") (pinfunction "1_1") (pintype "passive"))
      (node (ref "R11") (pin "2") (pinfunction "2_2") (pintype "passive"))
      (node (ref "R12") (pin "2") (pinfunction "2_2") (pintype "passive"))
      (node (ref "R13") (pin "2") (pinfunction "2_2") (pintype "passive"))
      (node (ref "R18") (pin "1") (pinfunction "1_1") (pintype "passive"))
      (node (ref "R19") (pin "1") (pinfunction "1_1") (pintype "passive"))
      (node (ref "R20") (pin "2") (pinfunction "2_2") (pintype "passive"))
      (node (ref "R21") (pin "2") (pinfunction "2_2") (pintype "passive"))
      (node (ref "R22") (pin "2") (pinfunction "2_2") (pintype "passive"))
      (node (ref "U3") (pin "28") (pinfunction "VDD_28") (pintype "power_in"))
    )
    (net (code "37") (name "VCC_3.3V_REG") (class "Default")
      (node (ref "C10") (pin "2") (pinfunction "2_2") (pintype "passive"))
      (node (ref "C19") (pin "1") (pinfunction "1_1") (pintype "passive"))
      (node (ref "C8") (pin "2") (pinfunction "2_2") (pintype "passive"))
      (node (ref "C9") (pin "2") (pinfunction "2_2") (pintype "passive"))
      (node (ref "FB1") (pin "2") (pinfunction "2_2") (pintype "passive"))
      (node (ref "FB2") (pin "2") (pinfunction "2_2") (pintype "passive"))
      (node (ref "IC1") (pin "2") (pinfunction "VOUT_2") (pintype "passive"))
    )
    (net (code "38") (name "unconnected-(IC1-NC-Pad4)") (class "Default")
      (node (ref "IC1") (pin "4") (pinfunction "NC_4") (pintype "passive"))
    )
    (net (code "39") (name "unconnected-(RJ1-NC-Pad7)") (class "Default")
      (node (ref "RJ1") (pin "7") (pinfunction "NC_7") (pintype "passive+no_connect"))
    )
    (net (code "40") (name "unconnected-(U3-DNC-Pad7)") (class "Default")
      (node (ref "U3") (pin "7") (pinfunction "DNC_7") (pintype "bidirectional+no_connect"))
    )
    (net (code "41") (name "unconnected-(U3-DUPLED-Pad26)") (class "Default")
      (node (ref "U3") (pin "26") (pinfunction "DUPLED_26") (pintype "output"))
    )
    (net (code "42") (name "unconnected-(U3-SPDLED-Pad24)") (class "Default")
      (node (ref "U3") (pin "24") (pinfunction "SPDLED_24") (pintype "output"))
    )
    (net (code "43") (name "unconnected-(U3-VBG-Pad18)") (class "Default")
      (node (ref "U3") (pin "18") (pinfunction "VBG_18") (pintype "output+no_connect"))
    )
  )
)
